# ctia.net
KiCad netlist of a schematic drawn in EAGLE
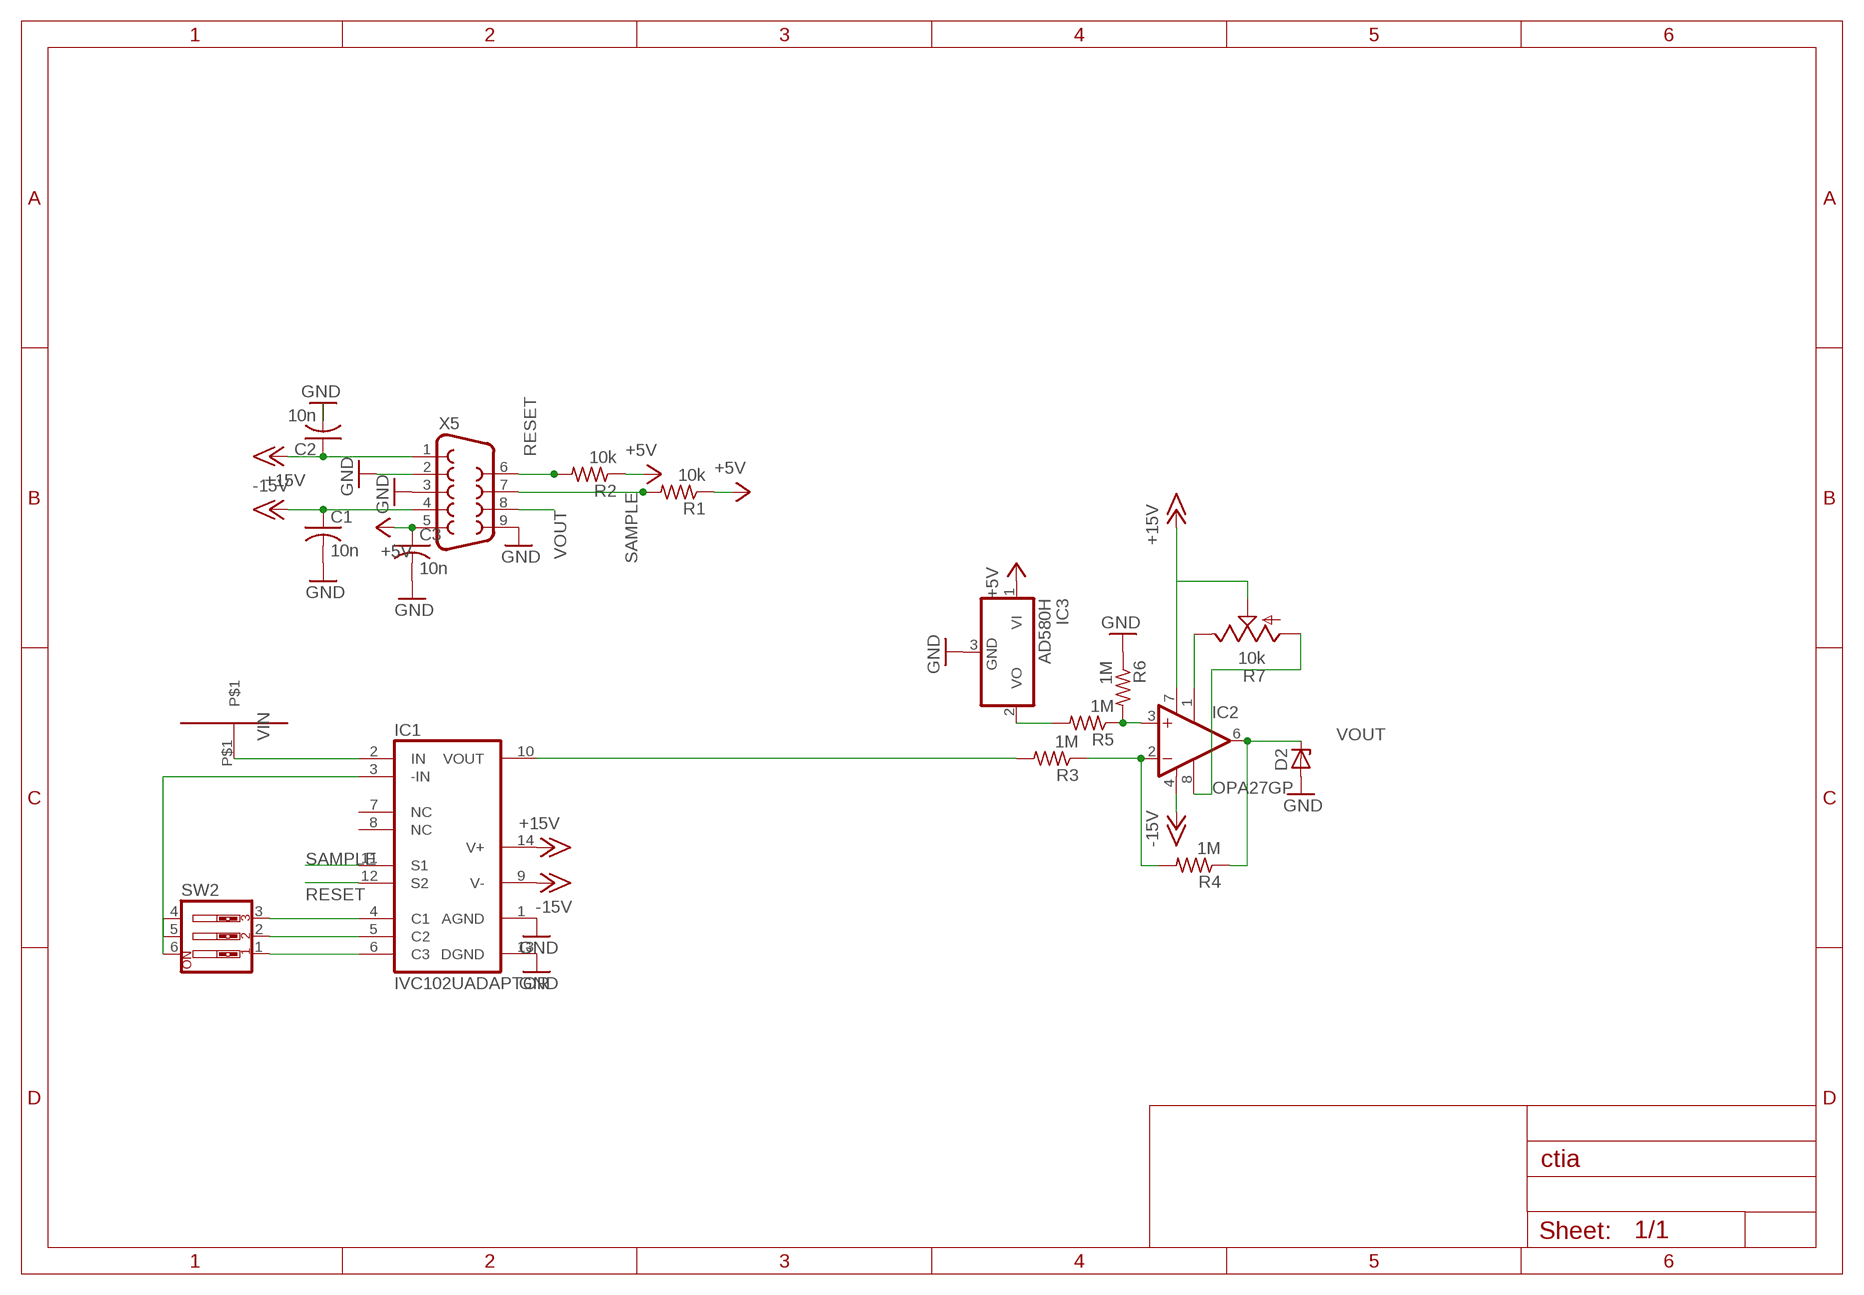
[diagram p0: schematic, sheet 1]

(export (version "E")
  (design (tool "Eeschema 10.0.6"))
  (components
    (comp (ref "C1")
      (value "10n")
      (footprint "eagle-import:C050-050X075")
      (libsource (lib "eagle-import") (part "C-US050-050X075"))
    )
    (comp (ref "C2")
      (value "10n")
      (footprint "eagle-import:C050-050X075")
      (libsource (lib "eagle-import") (part "C-US050-050X075"))
    )
    (comp (ref "C3")
      (value "10n")
      (footprint "eagle-import:C050-050X075")
      (libsource (lib "eagle-import") (part "C-US050-050X075"))
    )
    (comp (ref "D2")
      (value "ZENER-DIODEDO41Z10")
      (footprint "eagle-import:DO41Z10")
      (libsource (lib "eagle-import") (part "ZENER-DIODEDO41Z10"))
    )
    (comp (ref "IC1")
      (value "IVC102UADAPTOR")
      (footprint "eagle-import:DIL14")
      (libsource (lib "eagle-import") (part "IVC102UADAPTOR"))
    )
    (comp (ref "IC2")
      (value "OPA27GP")
      (footprint "eagle-import:DIL08")
      (libsource (lib "eagle-import") (part "OPA?GP27"))
    )
    (comp (ref "IC3")
      (value "AD580H")
      (footprint "eagle-import:TO39")
      (libsource (lib "eagle-import") (part "AD580H"))
    )
    (comp (ref "R1")
      (value "10k")
      (footprint "eagle-import:0207_15")
      (libsource (lib "eagle-import") (part "R-US_0207/15"))
    )
    (comp (ref "R2")
      (value "10k")
      (footprint "eagle-import:0207_15")
      (libsource (lib "eagle-import") (part "R-US_0207/15"))
    )
    (comp (ref "R3")
      (value "1M")
      (footprint "eagle-import:0207_10")
      (libsource (lib "eagle-import") (part "R-US_0207/10"))
    )
    (comp (ref "R4")
      (value "1M")
      (footprint "eagle-import:0207_10")
      (libsource (lib "eagle-import") (part "R-US_0207/10"))
    )
    (comp (ref "R5")
      (value "1M")
      (footprint "eagle-import:0207_10")
      (libsource (lib "eagle-import") (part "R-US_0207/10"))
    )
    (comp (ref "R6")
      (value "1M")
      (footprint "eagle-import:0207_10")
      (libsource (lib "eagle-import") (part "R-US_0207/10"))
    )
    (comp (ref "R7")
      (value "10k")
      (footprint "eagle-import:B64Y")
      (libsource (lib "eagle-import") (part "TRIM_US-B64Y"))
    )
    (comp (ref "SW2")
      (value "SW_DIP-3")
      (footprint "eagle-import:EDG-03")
      (libsource (lib "eagle-import") (part "SW_DIP-3"))
    )
    (comp (ref "U$1")
      (value "CTIA")
      (footprint "eagle-import:CTIA")
      (libsource (lib "eagle-import") (part "CTIA"))
    )
    (comp (ref "X5")
      (value "F09HP")
      (footprint "eagle-import:F09HP")
      (libsource (lib "eagle-import") (part "F09HP"))
    )
  )
  (nets
    (net (code "1") (name "+5V") (class "Default")
      (node (ref "C3") (pin "1") (pinfunction "1_1") (pintype "passive"))
      (node (ref "IC3") (pin "1") (pinfunction "VI_1") (pintype "input"))
      (node (ref "R1") (pin "1") (pinfunction "1_1") (pintype "passive"))
      (node (ref "R2") (pin "1") (pinfunction "1_1") (pintype "passive"))
      (node (ref "X5") (pin "5") (pinfunction "5_5") (pintype "passive"))
    )
    (net (code "2") (name "+15V") (class "Default")
      (node (ref "C2") (pin "1") (pinfunction "1_1") (pintype "passive"))
      (node (ref "IC1") (pin "14") (pinfunction "V+_14") (pintype "power_in"))
      (node (ref "IC2") (pin "7") (pinfunction "V+_7") (pintype "power_in"))
      (node (ref "R7") (pin "S") (pinfunction "S_S") (pintype "passive"))
      (node (ref "X5") (pin "1") (pinfunction "1_1") (pintype "passive"))
    )
    (net (code "3") (name "-15V") (class "Default")
      (node (ref "C1") (pin "1") (pinfunction "1_1") (pintype "passive"))
      (node (ref "IC1") (pin "9") (pinfunction "V-_9") (pintype "power_in"))
      (node (ref "IC2") (pin "4") (pinfunction "V-_4") (pintype "power_in"))
      (node (ref "X5") (pin "4") (pinfunction "4_4") (pintype "passive"))
    )
    (net (code "4") (name "/RESET") (class "Default")
      (node (ref "IC1") (pin "12") (pinfunction "S2_12") (pintype "input"))
      (node (ref "R2") (pin "2") (pinfunction "2_2") (pintype "passive"))
      (node (ref "X5") (pin "6") (pinfunction "6_6") (pintype "passive"))
    )
    (net (code "5") (name "/SAMPLE") (class "Default")
      (node (ref "IC1") (pin "11") (pinfunction "S1_11") (pintype "input"))
      (node (ref "R1") (pin "2") (pinfunction "2_2") (pintype "passive"))
      (node (ref "X5") (pin "7") (pinfunction "7_7") (pintype "passive"))
    )
    (net (code "6") (name "/VIN") (class "Default")
      (node (ref "IC1") (pin "2") (pinfunction "IN_2") (pintype "input"))
      (node (ref "U$1") (pin "P$1") (pinfunction "P$1_P$1") (pintype "bidirectional"))
    )
    (net (code "7") (name "/VOUT") (class "Default")
      (node (ref "D2") (pin "C") (pinfunction "C_C") (pintype "passive"))
      (node (ref "IC2") (pin "6") (pinfunction "OUT_6") (pintype "output"))
      (node (ref "R4") (pin "1") (pinfunction "1_1") (pintype "passive"))
      (node (ref "X5") (pin "8") (pinfunction "8_8") (pintype "passive"))
    )
    (net (code "8") (name "GND") (class "Default")
      (node (ref "C1") (pin "2") (pinfunction "2_2") (pintype "passive"))
      (node (ref "C2") (pin "2") (pinfunction "2_2") (pintype "passive"))
      (node (ref "C3") (pin "2") (pinfunction "2_2") (pintype "passive"))
      (node (ref "D2") (pin "A") (pinfunction "A_A") (pintype "passive"))
      (node (ref "IC1") (pin "1") (pinfunction "AGND_1") (pintype "power_in"))
      (node (ref "IC1") (pin "13") (pinfunction "DGND_13") (pintype "power_in"))
      (node (ref "IC3") (pin "3") (pinfunction "GND_3") (pintype "passive"))
      (node (ref "R6") (pin "1") (pinfunction "1_1") (pintype "passive"))
      (node (ref "X5") (pin "2") (pinfunction "2_2") (pintype "passive"))
      (node (ref "X5") (pin "3") (pinfunction "3_3") (pintype "passive"))
      (node (ref "X5") (pin "9") (pinfunction "9_9") (pintype "passive"))
    )
    (net (code "9") (name "Net-(IC1--IN)") (class "Default")
      (node (ref "IC1") (pin "3") (pinfunction "-IN_3") (pintype "input"))
      (node (ref "SW2") (pin "4") (pinfunction "4_4") (pintype "passive"))
      (node (ref "SW2") (pin "5") (pinfunction "5_5") (pintype "passive"))
      (node (ref "SW2") (pin "6") (pinfunction "6_6") (pintype "passive"))
    )
    (net (code "10") (name "Net-(IC1-C1)") (class "Default")
      (node (ref "IC1") (pin "4") (pinfunction "C1_4") (pintype "passive"))
      (node (ref "SW2") (pin "3") (pinfunction "3_3") (pintype "passive"))
    )
    (net (code "11") (name "Net-(IC1-C2)") (class "Default")
      (node (ref "IC1") (pin "5") (pinfunction "C2_5") (pintype "passive"))
      (node (ref "SW2") (pin "2") (pinfunction "2_2") (pintype "passive"))
    )
    (net (code "12") (name "Net-(IC1-C3)") (class "Default")
      (node (ref "IC1") (pin "6") (pinfunction "C3_6") (pintype "passive"))
      (node (ref "SW2") (pin "1") (pinfunction "1_1") (pintype "passive"))
    )
    (net (code "13") (name "Net-(IC1-VOUT)") (class "Default")
      (node (ref "IC1") (pin "10") (pinfunction "VOUT_10") (pintype "output"))
      (node (ref "R3") (pin "2") (pinfunction "2_2") (pintype "passive"))
    )
    (net (code "14") (name "Net-(IC2-+IN)") (class "Default")
      (node (ref "IC2") (pin "3") (pinfunction "+IN_3") (pintype "input"))
      (node (ref "R5") (pin "1") (pinfunction "1_1") (pintype "passive"))
      (node (ref "R6") (pin "2") (pinfunction "2_2") (pintype "passive"))
    )
    (net (code "15") (name "Net-(IC2--IN)") (class "Default")
      (node (ref "IC2") (pin "2") (pinfunction "-IN_2") (pintype "input"))
      (node (ref "R3") (pin "1") (pinfunction "1_1") (pintype "passive"))
      (node (ref "R4") (pin "2") (pinfunction "2_2") (pintype "passive"))
    )
    (net (code "16") (name "Net-(IC2-OFF1)") (class "Default")
      (node (ref "IC2") (pin "1") (pinfunction "OFF1_1") (pintype "passive"))
      (node (ref "R7") (pin "E") (pinfunction "E_E") (pintype "passive"))
    )
    (net (code "17") (name "Net-(IC2-OFF2)") (class "Default")
      (node (ref "IC2") (pin "8") (pinfunction "OFF2_8") (pintype "passive"))
      (node (ref "R7") (pin "A") (pinfunction "A_A") (pintype "passive"))
    )
    (net (code "18") (name "Net-(IC3-VO)") (class "Default")
      (node (ref "IC3") (pin "2") (pinfunction "VO_2") (pintype "passive"))
      (node (ref "R5") (pin "2") (pinfunction "2_2") (pintype "passive"))
    )
    (net (code "19") (name "unconnected-(IC1-NC-Pad7)") (class "Default")
      (node (ref "IC1") (pin "7") (pinfunction "NC_7") (pintype "no_connect"))
    )
    (net (code "20") (name "unconnected-(IC1-NC-Pad8)") (class "Default")
      (node (ref "IC1") (pin "8") (pinfunction "NC_8") (pintype "no_connect"))
    )
  )
)
